# pwr_brd_uni.net
KiCad netlist of a schematic drawn in EAGLE
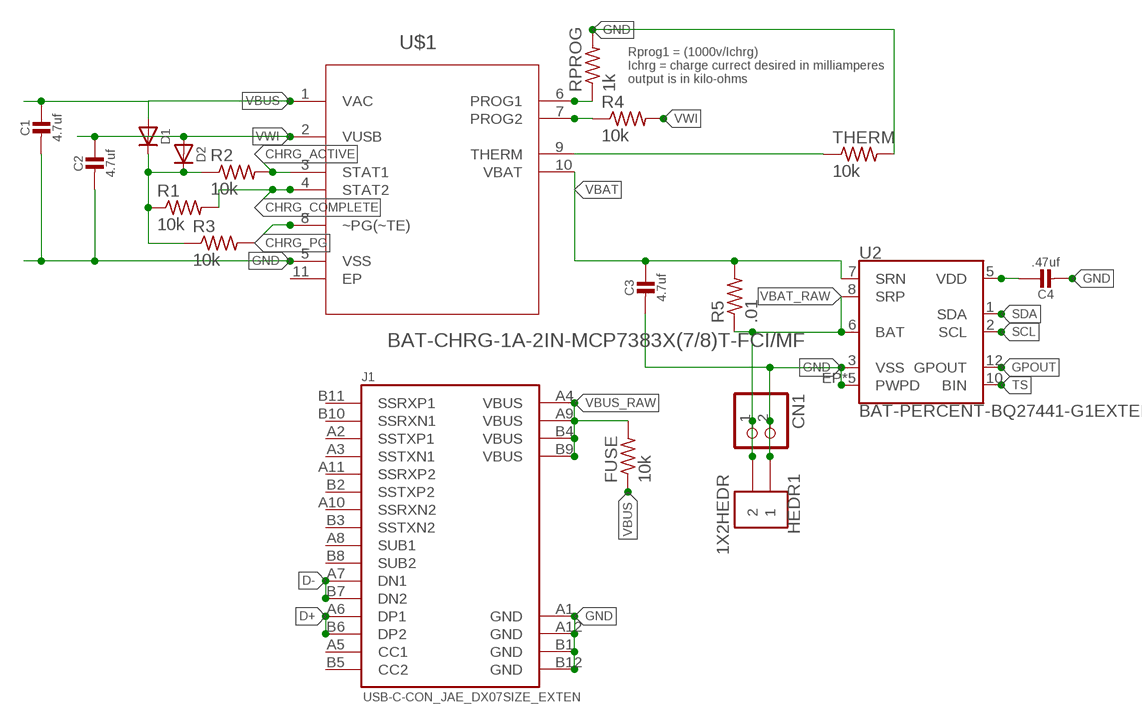
[diagram p0: schematic, sheet 1]

(export (version "E")
  (design (tool "Eeschema 10.0.6"))
  (components
    (comp (ref "C1")
      (value "4.7uf")
      (footprint "eagle-import:MICROBUILDER__0805MP")
      (libsource (lib "eagle-import") (part "C-US__0805MP"))
    )
    (comp (ref "C2")
      (value "4.7uf")
      (footprint "eagle-import:MICROBUILDER__0805MP")
      (libsource (lib "eagle-import") (part "C-US__0805MP"))
    )
    (comp (ref "C3")
      (value "4.7uf")
      (footprint "eagle-import:MICROBUILDER__0805MP")
      (libsource (lib "eagle-import") (part "C-US__0805MP"))
    )
    (comp (ref "C4")
      (value ".47uf")
      (footprint "eagle-import:MICROBUILDER__0805MP")
      (libsource (lib "eagle-import") (part "C-US__0805MP"))
    )
    (comp (ref "CN1")
      (value "JST_2PIN-SMT-RA")
      (footprint "eagle-import:JST-PH-2-SMT-RA")
      (libsource (lib "eagle-import") (part "JST_2PIN-SMT-RA"))
    )
    (comp (ref "D1")
      (value "DIODESOD-123")
      (footprint "eagle-import:SOD-123")
      (libsource (lib "eagle-import") (part "DIODESOD-123"))
    )
    (comp (ref "D2")
      (value "DIODESOD-123")
      (footprint "eagle-import:SOD-123")
      (libsource (lib "eagle-import") (part "DIODESOD-123"))
    )
    (comp (ref "FUSE")
      (value "10k")
      (footprint "eagle-import:R0805")
      (libsource (lib "eagle-import") (part "R-US_R0805"))
    )
    (comp (ref "HEDR1")
      (value "1X2HEDR")
      (footprint "eagle-import:1X2_HEDR")
      (libsource (lib "eagle-import") (part "1X2HEDR"))
    )
    (comp (ref "J1")
      (value "USB-C-CON_JAE_DX07SIZE_EXTEN")
      (footprint "eagle-import:JAE_DX07S024XJ1R1100_COMPLY_EXTEN")
      (libsource (lib "eagle-import") (part "USB-C-CON_JAE_DX07SIZE_EXTEN"))
    )
    (comp (ref "R1")
      (value "10k")
      (footprint "eagle-import:R0805")
      (libsource (lib "eagle-import") (part "R-US_R0805"))
    )
    (comp (ref "R2")
      (value "10k")
      (footprint "eagle-import:R0805")
      (libsource (lib "eagle-import") (part "R-US_R0805"))
    )
    (comp (ref "R3")
      (value "10k")
      (footprint "eagle-import:R0805")
      (libsource (lib "eagle-import") (part "R-US_R0805"))
    )
    (comp (ref "R4")
      (value "10k")
      (footprint "eagle-import:R0805")
      (libsource (lib "eagle-import") (part "R-US_R0805"))
    )
    (comp (ref "R5")
      (value ".01")
      (footprint "eagle-import:R0805")
      (libsource (lib "eagle-import") (part "R-US_R0805"))
    )
    (comp (ref "RPROG")
      (value "1k")
      (footprint "eagle-import:R0805")
      (libsource (lib "eagle-import") (part "R-US_R0805"))
    )
    (comp (ref "THERM")
      (value "10k")
      (footprint "eagle-import:R0805")
      (libsource (lib "eagle-import") (part "R-US_R0805"))
    )
    (comp (ref "U$1")
      (value "BAT-CHRG-1A-2IN-MCP7383X(7/8)T-FCI/MF")
      (footprint "eagle-import:DFN300X300X100-11N")
      (fields (field (name "MF") "Microchip") (field (name "MP") "MCP73837T-FCI/MF"))
      (libsource (lib "eagle-import") (part "BAT-CHRG-1A-2IN-MCP7383X(7/8)T-FCI/MF"))
    )
    (comp (ref "U2")
      (value "BAT-PERCENT-BQ27441-G1EXTEN")
      (footprint "eagle-import:BAT_PMIC_PDSO-N12-EXTENDED")
      (libsource (lib "eagle-import") (part "BAT-PERCENT-BQ27441-G1EXTEN"))
    )
  )
  (nets
    (net (code "1") (name "CHRG_ACTIVE") (class "Default")
      (node (ref "R2") (pin "2") (pinfunction "2_2") (pintype "passive"))
      (node (ref "U$1") (pin "3") (pinfunction "STAT1_3") (pintype "input"))
    )
    (net (code "2") (name "CHRG_COMPLETE") (class "Default")
      (node (ref "R1") (pin "2") (pinfunction "2_2") (pintype "passive"))
      (node (ref "U$1") (pin "4") (pinfunction "STAT2_4") (pintype "input"))
    )
    (net (code "3") (name "CHRG_PG") (class "Default")
      (node (ref "R3") (pin "2") (pinfunction "2_2") (pintype "passive"))
      (node (ref "U$1") (pin "8") (pinfunction "~{PG(}TE)_8") (pintype "input"))
    )
    (net (code "4") (name "D+") (class "Default")
      (node (ref "J1") (pin "A6") (pinfunction "DP1_A6") (pintype "bidirectional"))
      (node (ref "J1") (pin "B6") (pinfunction "DP2_B6") (pintype "bidirectional"))
    )
    (net (code "5") (name "D-") (class "Default")
      (node (ref "J1") (pin "A7") (pinfunction "DN1_A7") (pintype "bidirectional"))
      (node (ref "J1") (pin "B7") (pinfunction "DN2_B7") (pintype "bidirectional"))
    )
    (net (code "6") (name "GND") (class "Default")
      (node (ref "C1") (pin "2") (pinfunction "2_2") (pintype "passive"))
      (node (ref "C2") (pin "2") (pinfunction "2_2") (pintype "passive"))
      (node (ref "C3") (pin "2") (pinfunction "2_2") (pintype "passive"))
      (node (ref "C4") (pin "2") (pinfunction "2_2") (pintype "passive"))
      (node (ref "CN1") (pin "2") (pinfunction "1_2") (pintype "passive"))
      (node (ref "HEDR1") (pin "1") (pinfunction "1_1") (pintype "bidirectional"))
      (node (ref "J1") (pin "A1") (pinfunction "GND_A1") (pintype "power_in"))
      (node (ref "J1") (pin "A12") (pinfunction "GND_A12") (pintype "power_in"))
      (node (ref "J1") (pin "B1") (pinfunction "GND_B1") (pintype "power_in"))
      (node (ref "J1") (pin "B12") (pinfunction "GND_B12") (pintype "power_in"))
      (node (ref "RPROG") (pin "2") (pinfunction "2_2") (pintype "passive"))
      (node (ref "THERM") (pin "2") (pinfunction "2_2") (pintype "passive"))
      (node (ref "U$1") (pin "5") (pinfunction "VSS_5") (pintype "power_in"))
      (node (ref "U2") (pin "3") (pinfunction "VSS_3") (pintype "bidirectional"))
      (node (ref "U2") (pin "EP") (pinfunction "PWPD_EP") (pintype "bidirectional"))
      (node (ref "U2") (pin "EP1") (pinfunction "PWPD_EP1") (pintype "bidirectional"))
      (node (ref "U2") (pin "EP2") (pinfunction "PWPD_EP2") (pintype "bidirectional"))
      (node (ref "U2") (pin "EP3") (pinfunction "PWPD_EP3") (pintype "bidirectional"))
      (node (ref "U2") (pin "EP4") (pinfunction "PWPD_EP4") (pintype "bidirectional"))
    )
    (net (code "7") (name "GPOUT") (class "Default")
      (node (ref "U2") (pin "12") (pinfunction "GPOUT_12") (pintype "bidirectional"))
    )
    (net (code "8") (name "Net-(D1-PadC)") (class "Default")
      (node (ref "D1") (pin "C") (pinfunction "C_C") (pintype "passive"))
      (node (ref "D2") (pin "C") (pinfunction "C_C") (pintype "passive"))
      (node (ref "R1") (pin "1") (pinfunction "1_1") (pintype "passive"))
      (node (ref "R2") (pin "1") (pinfunction "1_1") (pintype "passive"))
      (node (ref "R3") (pin "1") (pinfunction "1_1") (pintype "passive"))
    )
    (net (code "9") (name "Net-(U$1-PROG1)") (class "Default")
      (node (ref "RPROG") (pin "1") (pinfunction "1_1") (pintype "passive"))
      (node (ref "U$1") (pin "6") (pinfunction "PROG1_6") (pintype "output"))
    )
    (net (code "10") (name "Net-(U$1-PROG2)") (class "Default")
      (node (ref "R4") (pin "1") (pinfunction "1_1") (pintype "passive"))
      (node (ref "U$1") (pin "7") (pinfunction "PROG2_7") (pintype "output"))
    )
    (net (code "11") (name "Net-(U$1-THERM)") (class "Default")
      (node (ref "THERM") (pin "1") (pinfunction "1_1") (pintype "passive"))
      (node (ref "U$1") (pin "9") (pinfunction "THERM_9") (pintype "output"))
    )
    (net (code "12") (name "Net-(U2-VDD)") (class "Default")
      (node (ref "C4") (pin "1") (pinfunction "1_1") (pintype "passive"))
      (node (ref "U2") (pin "5") (pinfunction "VDD_5") (pintype "bidirectional"))
    )
    (net (code "13") (name "SCL") (class "Default")
      (node (ref "U2") (pin "2") (pinfunction "SCL_2") (pintype "bidirectional"))
    )
    (net (code "14") (name "SDA") (class "Default")
      (node (ref "U2") (pin "1") (pinfunction "SDA_1") (pintype "bidirectional"))
    )
    (net (code "15") (name "TS") (class "Default")
      (node (ref "U2") (pin "10") (pinfunction "BIN_10") (pintype "bidirectional"))
    )
    (net (code "16") (name "VBAT") (class "Default")
      (node (ref "C3") (pin "1") (pinfunction "1_1") (pintype "passive"))
      (node (ref "R5") (pin "2") (pinfunction "2_2") (pintype "passive"))
      (node (ref "U$1") (pin "10") (pinfunction "VBAT_10") (pintype "output"))
      (node (ref "U2") (pin "7") (pinfunction "SRN_7") (pintype "bidirectional"))
    )
    (net (code "17") (name "VBAT_RAW") (class "Default")
      (node (ref "CN1") (pin "1") (pinfunction "2_1") (pintype "passive"))
      (node (ref "HEDR1") (pin "2") (pinfunction "2_2") (pintype "bidirectional"))
      (node (ref "R5") (pin "1") (pinfunction "1_1") (pintype "passive"))
      (node (ref "U2") (pin "6") (pinfunction "BAT_6") (pintype "bidirectional"))
      (node (ref "U2") (pin "8") (pinfunction "SRP_8") (pintype "bidirectional"))
    )
    (net (code "18") (name "VBUS") (class "Default")
      (node (ref "C1") (pin "1") (pinfunction "1_1") (pintype "passive"))
      (node (ref "D1") (pin "A") (pinfunction "A_A") (pintype "passive"))
      (node (ref "FUSE") (pin "1") (pinfunction "1_1") (pintype "passive"))
      (node (ref "U$1") (pin "1") (pinfunction "VAC_1") (pintype "input"))
    )
    (net (code "19") (name "VBUS_RAW") (class "Default")
      (node (ref "FUSE") (pin "2") (pinfunction "2_2") (pintype "passive"))
      (node (ref "J1") (pin "A4") (pinfunction "VBUS_A4") (pintype "power_in"))
      (node (ref "J1") (pin "A9") (pinfunction "VBUS_A9") (pintype "power_in"))
      (node (ref "J1") (pin "B4") (pinfunction "VBUS_B4") (pintype "power_in"))
      (node (ref "J1") (pin "B9") (pinfunction "VBUS_B9") (pintype "power_in"))
    )
    (net (code "20") (name "VWI") (class "Default")
      (node (ref "C2") (pin "1") (pinfunction "1_1") (pintype "passive"))
      (node (ref "D2") (pin "A") (pinfunction "A_A") (pintype "passive"))
      (node (ref "R4") (pin "2") (pinfunction "2_2") (pintype "passive"))
      (node (ref "U$1") (pin "2") (pinfunction "VUSB_2") (pintype "input"))
    )
    (net (code "21") (name "unconnected-(J1-CC1-PadA5)") (class "Default")
      (node (ref "J1") (pin "A5") (pinfunction "CC1_A5") (pintype "bidirectional"))
    )
    (net (code "22") (name "unconnected-(J1-CC2-PadB5)") (class "Default")
      (node (ref "J1") (pin "B5") (pinfunction "CC2_B5") (pintype "bidirectional"))
    )
    (net (code "23") (name "unconnected-(J1-SSRXN1-PadB10)") (class "Default")
      (node (ref "J1") (pin "B10") (pinfunction "SSRXN1_B10") (pintype "bidirectional"))
    )
    (net (code "24") (name "unconnected-(J1-SSRXN2-PadA10)") (class "Default")
      (node (ref "J1") (pin "A10") (pinfunction "SSRXN2_A10") (pintype "bidirectional"))
    )
    (net (code "25") (name "unconnected-(J1-SSRXP1-PadB11)") (class "Default")
      (node (ref "J1") (pin "B11") (pinfunction "SSRXP1_B11") (pintype "bidirectional"))
    )
    (net (code "26") (name "unconnected-(J1-SSRXP2-PadA11)") (class "Default")
      (node (ref "J1") (pin "A11") (pinfunction "SSRXP2_A11") (pintype "bidirectional"))
    )
    (net (code "27") (name "unconnected-(J1-SSTXN1-PadA3)") (class "Default")
      (node (ref "J1") (pin "A3") (pinfunction "SSTXN1_A3") (pintype "bidirectional"))
    )
    (net (code "28") (name "unconnected-(J1-SSTXN2-PadB3)") (class "Default")
      (node (ref "J1") (pin "B3") (pinfunction "SSTXN2_B3") (pintype "bidirectional"))
    )
    (net (code "29") (name "unconnected-(J1-SSTXP1-PadA2)") (class "Default")
      (node (ref "J1") (pin "A2") (pinfunction "SSTXP1_A2") (pintype "bidirectional"))
    )
    (net (code "30") (name "unconnected-(J1-SSTXP2-PadB2)") (class "Default")
      (node (ref "J1") (pin "B2") (pinfunction "SSTXP2_B2") (pintype "bidirectional"))
    )
    (net (code "31") (name "unconnected-(J1-SUB1-PadA8)") (class "Default")
      (node (ref "J1") (pin "A8") (pinfunction "SUB1_A8") (pintype "bidirectional"))
    )
    (net (code "32") (name "unconnected-(J1-SUB2-PadB8)") (class "Default")
      (node (ref "J1") (pin "B8") (pinfunction "SUB2_B8") (pintype "bidirectional"))
    )
    (net (code "33") (name "unconnected-(U$1-EP-Pad11)") (class "Default")
      (node (ref "U$1") (pin "11") (pinfunction "EP_11") (pintype "passive"))
    )
  )
)
